# CombinedSchem.net
KiCad netlist of a schematic drawn in EAGLE
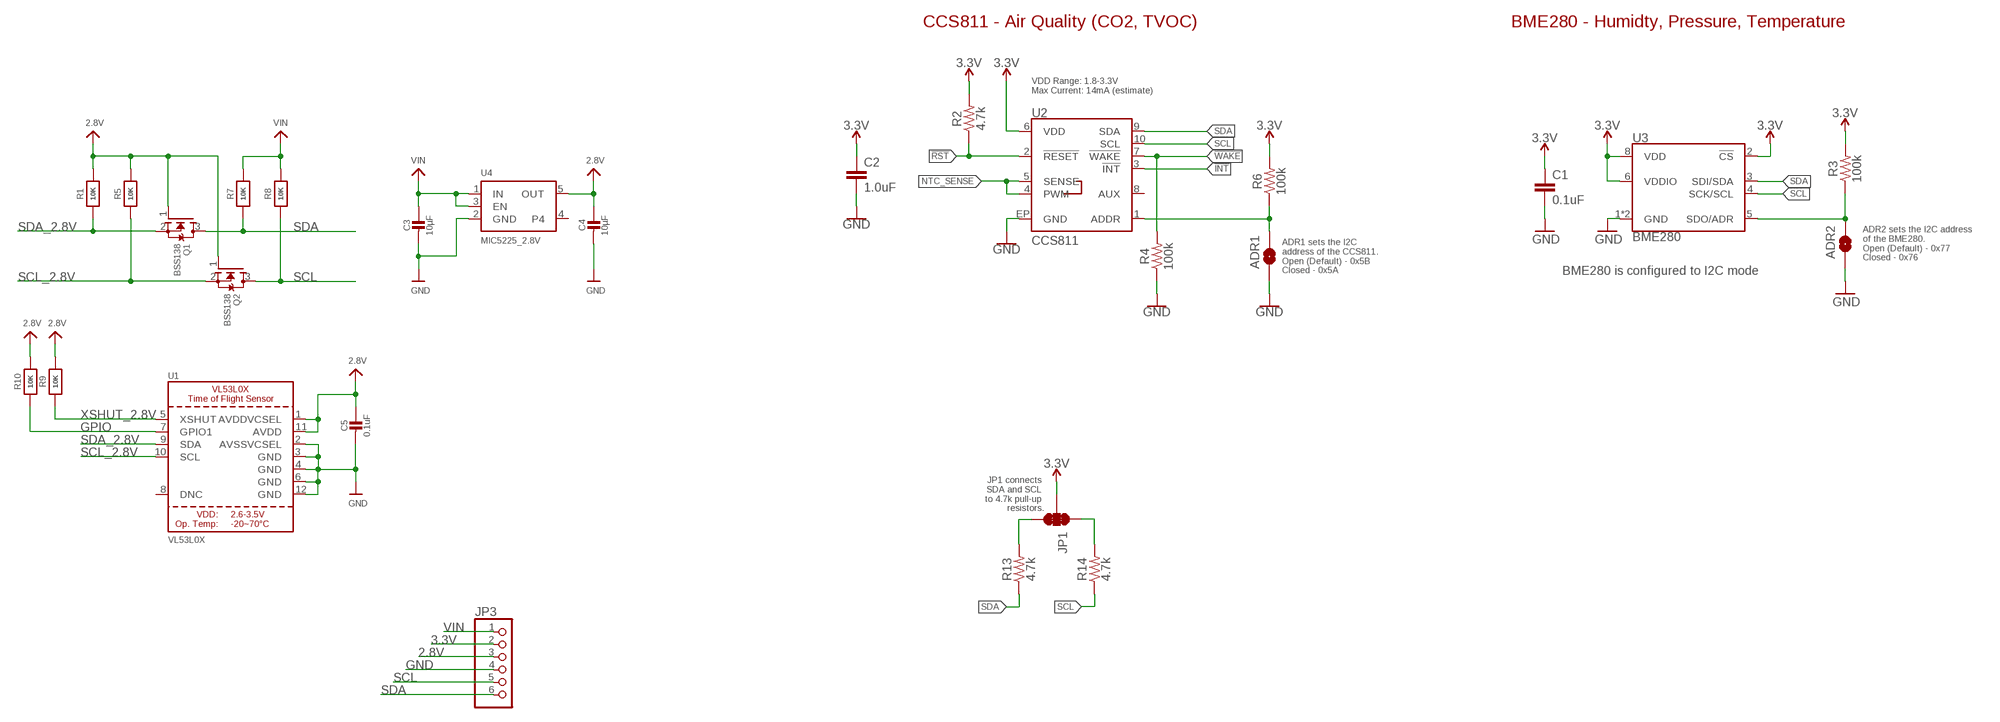
[diagram p0: schematic, sheet 1]

(export (version "E")
  (design (tool "Eeschema 10.0.6"))
  (components
    (comp (ref "ADR1")
      (value "JUMPER-SMT_2_NO_SILK")
      (footprint "eagle-import:SMT-JUMPER_2_NO_SILK")
      (libsource (lib "eagle-import") (part "JUMPER-SMT_2_NO_SILK"))
    )
    (comp (ref "ADR2")
      (value "JUMPER-SMT_2_NO_SILK")
      (footprint "eagle-import:SMT-JUMPER_2_NO_SILK")
      (libsource (lib "eagle-import") (part "JUMPER-SMT_2_NO_SILK"))
    )
    (comp (ref "C1")
      (value "0.1uF")
      (footprint "eagle-import:0603")
      (libsource (lib "eagle-import") (part "0.1UF-0603-25V-(+80/-20%)"))
    )
    (comp (ref "C2")
      (value "1.0uF")
      (footprint "eagle-import:0603")
      (libsource (lib "eagle-import") (part "1.0UF-0603-16V-10%"))
    )
    (comp (ref "C3")
      (value "10µF")
      (footprint "eagle-import:0805-NO")
      (libsource (lib "eagle-import") (part "CAP_CERAMIC0805-NOOUTLINE"))
    )
    (comp (ref "C4")
      (value "10µF")
      (footprint "eagle-import:0805-NO")
      (libsource (lib "eagle-import") (part "CAP_CERAMIC0805-NOOUTLINE"))
    )
    (comp (ref "C5")
      (value "0.1uF")
      (footprint "eagle-import:0805-NO")
      (libsource (lib "eagle-import") (part "CAP_CERAMIC0805-NOOUTLINE"))
    )
    (comp (ref "JP1")
      (value "JUMPER-SMT_3_2-NC_TRACE_SILK")
      (footprint "eagle-import:SMT-JUMPER_3_2-NC_TRACE_SILK")
      (libsource (lib "eagle-import") (part "JUMPER-SMT_3_2-NC_TRACE_SILK"))
    )
    (comp (ref "JP3")
      (value "PINHD-1X6CLEAN")
      (footprint "eagle-import:1X06-CLEAN")
      (libsource (lib "eagle-import") (part "PINHD-1X6CLEAN"))
    )
    (comp (ref "Q1")
      (value "BSS138")
      (footprint "eagle-import:SOT23-WIDE")
      (libsource (lib "eagle-import") (part "MOSFET-NWIDE"))
    )
    (comp (ref "Q2")
      (value "BSS138")
      (footprint "eagle-import:SOT23-WIDE")
      (libsource (lib "eagle-import") (part "MOSFET-NWIDE"))
    )
    (comp (ref "R1")
      (value "10K")
      (footprint "eagle-import:0805-NO")
      (libsource (lib "eagle-import") (part "RESISTOR0805_NOOUTLINE"))
    )
    (comp (ref "R2")
      (value "4.7k")
      (footprint "eagle-import:0603")
      (libsource (lib "eagle-import") (part "4.7KOHM-0603-1/10W-1%"))
    )
    (comp (ref "R3")
      (value "100k")
      (footprint "eagle-import:0603")
      (libsource (lib "eagle-import") (part "100KOHM-0603-1/10W-1%"))
    )
    (comp (ref "R4")
      (value "100k")
      (footprint "eagle-import:0603")
      (libsource (lib "eagle-import") (part "100KOHM-0603-1/10W-1%"))
    )
    (comp (ref "R5")
      (value "10K")
      (footprint "eagle-import:0805-NO")
      (libsource (lib "eagle-import") (part "RESISTOR0805_NOOUTLINE"))
    )
    (comp (ref "R6")
      (value "100k")
      (footprint "eagle-import:0603")
      (libsource (lib "eagle-import") (part "100KOHM-0603-1/10W-1%"))
    )
    (comp (ref "R7")
      (value "10K")
      (footprint "eagle-import:0805-NO")
      (libsource (lib "eagle-import") (part "RESISTOR0805_NOOUTLINE"))
    )
    (comp (ref "R8")
      (value "10K")
      (footprint "eagle-import:0805-NO")
      (libsource (lib "eagle-import") (part "RESISTOR0805_NOOUTLINE"))
    )
    (comp (ref "R9")
      (value "10K")
      (footprint "eagle-import:0805-NO")
      (libsource (lib "eagle-import") (part "RESISTOR0805_NOOUTLINE"))
    )
    (comp (ref "R10")
      (value "10K")
      (footprint "eagle-import:0805-NO")
      (libsource (lib "eagle-import") (part "RESISTOR0805_NOOUTLINE"))
    )
    (comp (ref "R13")
      (value "4.7k")
      (footprint "eagle-import:0603")
      (libsource (lib "eagle-import") (part "4.7KOHM-0603-1/10W-1%"))
    )
    (comp (ref "R14")
      (value "4.7k")
      (footprint "eagle-import:0603")
      (libsource (lib "eagle-import") (part "4.7KOHM-0603-1/10W-1%"))
    )
    (comp (ref "U1")
      (value "VL53L0X")
      (footprint "eagle-import:LGA12_ST")
      (libsource (lib "eagle-import") (part "VL53L0X"))
    )
    (comp (ref "U2")
      (value "CCS811")
      (footprint "eagle-import:LGA10")
      (libsource (lib "eagle-import") (part "CCS811PRODUCTION"))
    )
    (comp (ref "U3")
      (value "BME280")
      (footprint "eagle-import:LGA-8-2.5X2.5")
      (libsource (lib "eagle-import") (part "BME280"))
    )
    (comp (ref "U4")
      (value "MIC5225_2.8V")
      (footprint "eagle-import:SOT23-5")
      (libsource (lib "eagle-import") (part "VREG_SOT23-5"))
    )
  )
  (nets
    (net (code "1") (name "/GPIO") (class "Default")
      (node (ref "R10") (pin "1") (pinfunction "1_1") (pintype "passive"))
      (node (ref "U1") (pin "7") (pinfunction "GPIO1_7") (pintype "output"))
    )
    (net (code "2") (name "/SCL_2.8V") (class "Default")
      (node (ref "Q2") (pin "2") (pinfunction "S_2") (pintype "bidirectional"))
      (node (ref "R5") (pin "1") (pinfunction "1_1") (pintype "passive"))
      (node (ref "U1") (pin "10") (pinfunction "SCL_10") (pintype "open_collector"))
    )
    (net (code "3") (name "/SDA_2.8V") (class "Default")
      (node (ref "Q1") (pin "2") (pinfunction "S_2") (pintype "bidirectional"))
      (node (ref "R1") (pin "1") (pinfunction "1_1") (pintype "passive"))
      (node (ref "U1") (pin "9") (pinfunction "SDA_9") (pintype "open_collector"))
    )
    (net (code "4") (name "/XSHUT_2.8V") (class "Default")
      (node (ref "R9") (pin "1") (pinfunction "1_1") (pintype "passive"))
      (node (ref "U1") (pin "5") (pinfunction "XSHUT_5") (pintype "input"))
    )
    (net (code "5") (name "/~{INT}") (class "Default")
      (node (ref "U2") (pin "3") (pinfunction "~{INT}_3") (pintype "bidirectional"))
    )
    (net (code "6") (name "/~{RST}") (class "Default")
      (node (ref "R2") (pin "1") (pinfunction "1_1") (pintype "passive"))
      (node (ref "U2") (pin "2") (pinfunction "~{RESET}_2") (pintype "bidirectional"))
    )
    (net (code "7") (name "/~{WAKE}") (class "Default")
      (node (ref "R4") (pin "2") (pinfunction "2_2") (pintype "passive"))
      (node (ref "U2") (pin "7") (pinfunction "~{WAKE}_7") (pintype "bidirectional"))
    )
    (net (code "8") (name "2.8V") (class "Default")
      (node (ref "C4") (pin "1") (pinfunction "1_1") (pintype "passive"))
      (node (ref "C5") (pin "1") (pinfunction "1_1") (pintype "passive"))
      (node (ref "JP3") (pin "3") (pinfunction "3_3") (pintype "passive"))
      (node (ref "Q1") (pin "1") (pinfunction "G_1") (pintype "bidirectional"))
      (node (ref "Q2") (pin "1") (pinfunction "G_1") (pintype "bidirectional"))
      (node (ref "R1") (pin "2") (pinfunction "2_2") (pintype "passive"))
      (node (ref "R10") (pin "2") (pinfunction "2_2") (pintype "passive"))
      (node (ref "R5") (pin "2") (pinfunction "2_2") (pintype "passive"))
      (node (ref "R9") (pin "2") (pinfunction "2_2") (pintype "passive"))
      (node (ref "U1") (pin "1") (pinfunction "AVDDVCSEL_1") (pintype "power_in"))
      (node (ref "U1") (pin "11") (pinfunction "AVDD_11") (pintype "power_in"))
      (node (ref "U4") (pin "5") (pinfunction "OUT_5") (pintype "power_in"))
    )
    (net (code "9") (name "3.3V") (class "Default")
      (node (ref "C1") (pin "1") (pinfunction "1_1") (pintype "passive"))
      (node (ref "C2") (pin "1") (pinfunction "1_1") (pintype "passive"))
      (node (ref "JP1") (pin "2") (pinfunction "2_2") (pintype "passive"))
      (node (ref "JP3") (pin "2") (pinfunction "2_2") (pintype "passive"))
      (node (ref "R2") (pin "2") (pinfunction "2_2") (pintype "passive"))
      (node (ref "R3") (pin "2") (pinfunction "2_2") (pintype "passive"))
      (node (ref "R6") (pin "2") (pinfunction "2_2") (pintype "passive"))
      (node (ref "U2") (pin "6") (pinfunction "VDD_6") (pintype "bidirectional"))
      (node (ref "U3") (pin "2") (pinfunction "~{CS}_2") (pintype "bidirectional"))
      (node (ref "U3") (pin "6") (pinfunction "VDDIO_6") (pintype "bidirectional"))
      (node (ref "U3") (pin "8") (pinfunction "VDD_8") (pintype "bidirectional"))
    )
    (net (code "10") (name "GND") (class "Default")
      (node (ref "ADR1") (pin "1") (pinfunction "1_1") (pintype "passive"))
      (node (ref "ADR2") (pin "1") (pinfunction "1_1") (pintype "passive"))
      (node (ref "C1") (pin "2") (pinfunction "2_2") (pintype "passive"))
      (node (ref "C2") (pin "2") (pinfunction "2_2") (pintype "passive"))
      (node (ref "C3") (pin "2") (pinfunction "2_2") (pintype "passive"))
      (node (ref "C4") (pin "2") (pinfunction "2_2") (pintype "passive"))
      (node (ref "C5") (pin "2") (pinfunction "2_2") (pintype "passive"))
      (node (ref "JP3") (pin "4") (pinfunction "4_4") (pintype "passive"))
      (node (ref "R4") (pin "1") (pinfunction "1_1") (pintype "passive"))
      (node (ref "U1") (pin "12") (pinfunction "GND_12") (pintype "power_in"))
      (node (ref "U1") (pin "2") (pinfunction "AVSSVCSEL_2") (pintype "power_in"))
      (node (ref "U1") (pin "3") (pinfunction "GND_3") (pintype "power_in"))
      (node (ref "U1") (pin "4") (pinfunction "GND_4") (pintype "power_in"))
      (node (ref "U1") (pin "6") (pinfunction "GND_6") (pintype "power_in"))
      (node (ref "U2") (pin "EP") (pinfunction "GND_EP") (pintype "bidirectional"))
      (node (ref "U3") (pin "1") (pinfunction "GND_1") (pintype "bidirectional"))
      (node (ref "U3") (pin "7") (pinfunction "GND_7") (pintype "bidirectional"))
      (node (ref "U4") (pin "2") (pinfunction "GND_2") (pintype "power_in"))
    )
    (net (code "11") (name "NTC_SENSE") (class "Default")
      (node (ref "U2") (pin "4") (pinfunction "PWM_4") (pintype "bidirectional"))
      (node (ref "U2") (pin "5") (pinfunction "SENSE_5") (pintype "bidirectional"))
    )
    (net (code "12") (name "Net-(JP1-Pad1)") (class "Default")
      (node (ref "JP1") (pin "1") (pinfunction "1_1") (pintype "passive"))
      (node (ref "R14") (pin "2") (pinfunction "2_2") (pintype "passive"))
    )
    (net (code "13") (name "Net-(JP1-Pad3)") (class "Default")
      (node (ref "JP1") (pin "3") (pinfunction "3_3") (pintype "passive"))
      (node (ref "R13") (pin "2") (pinfunction "2_2") (pintype "passive"))
    )
    (net (code "14") (name "Net-(U2-ADDR)") (class "Default")
      (node (ref "ADR1") (pin "2") (pinfunction "2_2") (pintype "passive"))
      (node (ref "R6") (pin "1") (pinfunction "1_1") (pintype "passive"))
      (node (ref "U2") (pin "1") (pinfunction "ADDR_1") (pintype "bidirectional"))
    )
    (net (code "15") (name "Net-(U3-SDO{slash}ADR)") (class "Default")
      (node (ref "ADR2") (pin "2") (pinfunction "2_2") (pintype "passive"))
      (node (ref "R3") (pin "1") (pinfunction "1_1") (pintype "passive"))
      (node (ref "U3") (pin "5") (pinfunction "SDO/ADR_5") (pintype "bidirectional"))
    )
    (net (code "16") (name "SCL") (class "Default")
      (node (ref "JP3") (pin "5") (pinfunction "5_5") (pintype "passive"))
      (node (ref "Q2") (pin "3") (pinfunction "D_3") (pintype "bidirectional"))
      (node (ref "R14") (pin "1") (pinfunction "1_1") (pintype "passive"))
      (node (ref "R8") (pin "1") (pinfunction "1_1") (pintype "passive"))
      (node (ref "U2") (pin "10") (pinfunction "SCL_10") (pintype "bidirectional"))
      (node (ref "U3") (pin "4") (pinfunction "SCK/SCL_4") (pintype "bidirectional"))
    )
    (net (code "17") (name "SDA") (class "Default")
      (node (ref "JP3") (pin "6") (pinfunction "6_6") (pintype "passive"))
      (node (ref "Q1") (pin "3") (pinfunction "D_3") (pintype "bidirectional"))
      (node (ref "R13") (pin "1") (pinfunction "1_1") (pintype "passive"))
      (node (ref "R7") (pin "1") (pinfunction "1_1") (pintype "passive"))
      (node (ref "U2") (pin "9") (pinfunction "SDA_9") (pintype "bidirectional"))
      (node (ref "U3") (pin "3") (pinfunction "SDI/SDA_3") (pintype "bidirectional"))
    )
    (net (code "18") (name "VIN") (class "Default")
      (node (ref "C3") (pin "1") (pinfunction "1_1") (pintype "passive"))
      (node (ref "JP3") (pin "1") (pinfunction "1_1") (pintype "passive"))
      (node (ref "R7") (pin "2") (pinfunction "2_2") (pintype "passive"))
      (node (ref "R8") (pin "2") (pinfunction "2_2") (pintype "passive"))
      (node (ref "U4") (pin "1") (pinfunction "IN_1") (pintype "power_in"))
      (node (ref "U4") (pin "3") (pinfunction "EN_3") (pintype "input"))
    )
    (net (code "19") (name "unconnected-(U1-DNC-Pad8)") (class "Default")
      (node (ref "U1") (pin "8") (pinfunction "DNC_8") (pintype "no_connect"))
    )
    (net (code "20") (name "unconnected-(U2-AUX-Pad8)") (class "Default")
      (node (ref "U2") (pin "8") (pinfunction "AUX_8") (pintype "bidirectional"))
    )
    (net (code "21") (name "unconnected-(U4-P4-Pad4)") (class "Default")
      (node (ref "U4") (pin "4") (pinfunction "P4_4") (pintype "bidirectional"))
    )
  )
)
